# converter.net
KiCad netlist of a schematic drawn in EAGLE
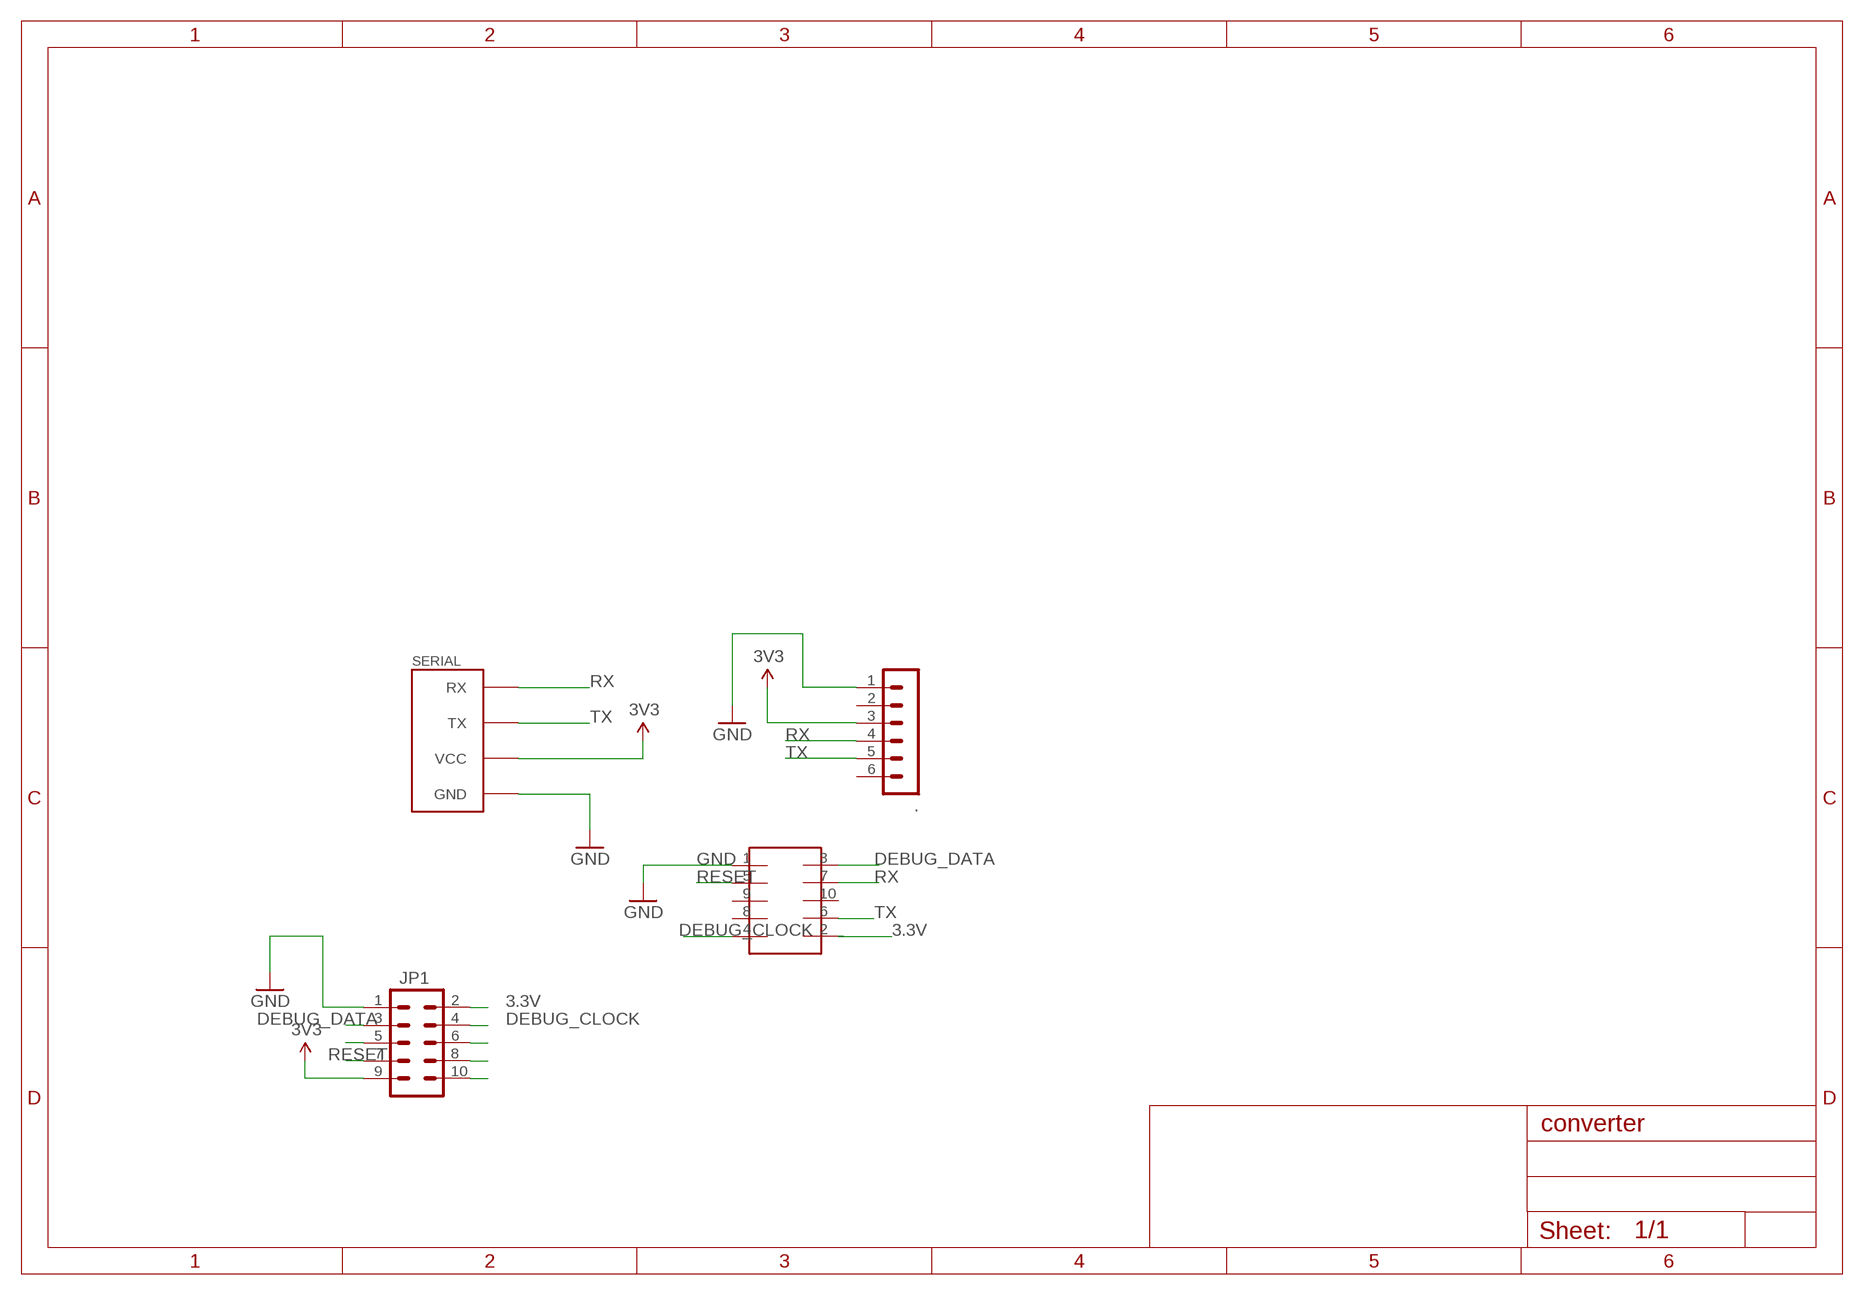
[diagram p0: schematic, sheet 1]

(export (version "E")
  (design (tool "Eeschema 10.0.6"))
  (components
    (comp (ref ".")
      (value "MA06-1")
      (footprint "eagle-import:MA06-1")
      (libsource (lib "eagle-import") (part "MA06-1"))
    )
    (comp (ref "JP1")
      (value "M05X2SHD")
      (footprint "eagle-import:2X5-SHROUDED")
      (libsource (lib "eagle-import") (part "M05X2SHD"))
    )
    (comp (ref "SERIAL")
      (value "FABO_BRICK_SERIAL-CONNECTOR_I")
      (footprint "eagle-import:FABO_BRICK_SERIAL_CONNECTOR_I")
      (libsource (lib "eagle-import") (part "FABO_BRICK_SERIAL-CONNECTOR_I"))
    )
    (comp (ref "U$4")
      (value "TC-2050-SOCKET")
      (footprint "eagle-import:TC-2050-SOCKET")
      (libsource (lib "eagle-import") (part "TC-2050-SOCKET"))
    )
  )
  (nets
    (net (code "1") (name "/3.3V") (class "Default")
      (node (ref "JP1") (pin "2") (pinfunction "2_2") (pintype "passive"))
      (node (ref "U$4") (pin "2") (pinfunction "2_2") (pintype "bidirectional"))
    )
    (net (code "2") (name "/DEBUG_CLOCK") (class "Default")
      (node (ref "JP1") (pin "4") (pinfunction "4_4") (pintype "passive"))
      (node (ref "U$4") (pin "4") (pinfunction "4_4") (pintype "bidirectional"))
    )
    (net (code "3") (name "/DEBUG_DATA") (class "Default")
      (node (ref "JP1") (pin "3") (pinfunction "3_3") (pintype "passive"))
      (node (ref "U$4") (pin "3") (pinfunction "3_3") (pintype "bidirectional"))
    )
    (net (code "4") (name "/RESET") (class "Default")
      (node (ref "JP1") (pin "7") (pinfunction "7_7") (pintype "passive"))
      (node (ref "U$4") (pin "5") (pinfunction "5_5") (pintype "bidirectional"))
    )
    (net (code "5") (name "/RX") (class "Default")
      (node (ref ".") (pin "4") (pinfunction "4_4") (pintype "passive"))
      (node (ref "SERIAL") (pin "RX") (pinfunction "RX_RX") (pintype "bidirectional"))
      (node (ref "U$4") (pin "7") (pinfunction "7_7") (pintype "bidirectional"))
    )
    (net (code "6") (name "/TX") (class "Default")
      (node (ref ".") (pin "5") (pinfunction "5_5") (pintype "passive"))
      (node (ref "SERIAL") (pin "TX") (pinfunction "TX_TX") (pintype "bidirectional"))
      (node (ref "U$4") (pin "6") (pinfunction "6_6") (pintype "bidirectional"))
    )
    (net (code "7") (name "3V3") (class "Default")
      (node (ref ".") (pin "3") (pinfunction "3_3") (pintype "passive"))
      (node (ref "JP1") (pin "9") (pinfunction "9_9") (pintype "passive"))
      (node (ref "SERIAL") (pin "VCC") (pinfunction "VCC_VCC") (pintype "bidirectional"))
    )
    (net (code "8") (name "GND") (class "Default")
      (node (ref ".") (pin "1") (pinfunction "1_1") (pintype "passive"))
      (node (ref "JP1") (pin "1") (pinfunction "1_1") (pintype "passive"))
      (node (ref "SERIAL") (pin "GND") (pinfunction "GND_GND") (pintype "bidirectional"))
      (node (ref "U$4") (pin "1") (pinfunction "1_1") (pintype "bidirectional"))
    )
    (net (code "9") (name "unconnected-(.-Pad2)") (class "Default")
      (node (ref ".") (pin "2") (pinfunction "2_2") (pintype "passive"))
    )
    (net (code "10") (name "unconnected-(.-Pad6)") (class "Default")
      (node (ref ".") (pin "6") (pinfunction "6_6") (pintype "passive"))
    )
    (net (code "11") (name "unconnected-(JP1-Pad5)") (class "Default")
      (node (ref "JP1") (pin "5") (pinfunction "5_5") (pintype "passive"))
    )
    (net (code "12") (name "unconnected-(JP1-Pad6)") (class "Default")
      (node (ref "JP1") (pin "6") (pinfunction "6_6") (pintype "passive"))
    )
    (net (code "13") (name "unconnected-(JP1-Pad8)") (class "Default")
      (node (ref "JP1") (pin "8") (pinfunction "8_8") (pintype "passive"))
    )
    (net (code "14") (name "unconnected-(JP1-Pad10)") (class "Default")
      (node (ref "JP1") (pin "10") (pinfunction "10_10") (pintype "passive"))
    )
    (net (code "15") (name "unconnected-(U$4-Pad8)") (class "Default")
      (node (ref "U$4") (pin "8") (pinfunction "8_8") (pintype "bidirectional"))
    )
    (net (code "16") (name "unconnected-(U$4-Pad9)") (class "Default")
      (node (ref "U$4") (pin "9") (pinfunction "9_9") (pintype "bidirectional"))
    )
    (net (code "17") (name "unconnected-(U$4-Pad10)") (class "Default")
      (node (ref "U$4") (pin "10") (pinfunction "10_10") (pintype "bidirectional"))
    )
  )
)
